# color_sensor.net
KiCad netlist of a schematic drawn in EAGLE
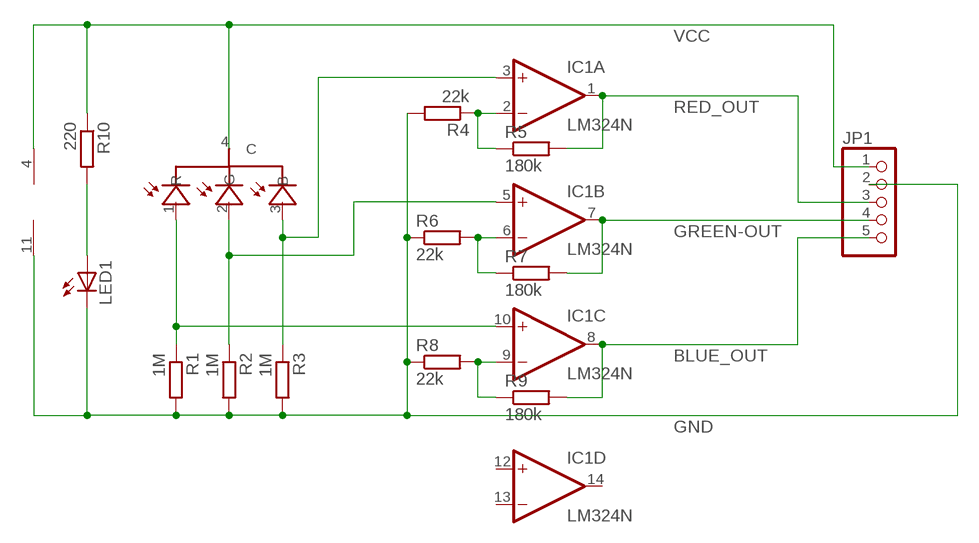
[diagram p0: schematic, sheet 1]

(export (version "E")
  (design (tool "Eeschema 10.0.6"))
  (components
    (comp (ref "IC1")
      (value "LM324N")
      (footprint "eagle-import:DIL14")
      (libsource (lib "eagle-import") (part "LM324N"))
    )
    (comp (ref "JP1")
      (value "PINHD-1X5")
      (footprint "eagle-import:1X05")
      (libsource (lib "eagle-import") (part "PINHD-1X5"))
    )
    (comp (ref "LED1")
      (value "LED5MM")
      (footprint "eagle-import:LED5MM")
      (libsource (lib "eagle-import") (part "LED5MM"))
    )
    (comp (ref "R1")
      (value "1M")
      (footprint "eagle-import:0207_10")
      (libsource (lib "eagle-import") (part "R-EU_0207/10"))
    )
    (comp (ref "R2")
      (value "1M")
      (footprint "eagle-import:0207_10")
      (libsource (lib "eagle-import") (part "R-EU_0207/10"))
    )
    (comp (ref "R3")
      (value "1M")
      (footprint "eagle-import:0207_10")
      (libsource (lib "eagle-import") (part "R-EU_0207/10"))
    )
    (comp (ref "R4")
      (value "22k")
      (footprint "eagle-import:0207_10")
      (libsource (lib "eagle-import") (part "R-EU_0207/10"))
    )
    (comp (ref "R5")
      (value "180k")
      (footprint "eagle-import:0207_10")
      (libsource (lib "eagle-import") (part "R-EU_0207/10"))
    )
    (comp (ref "R6")
      (value "22k")
      (footprint "eagle-import:0207_10")
      (libsource (lib "eagle-import") (part "R-EU_0207/10"))
    )
    (comp (ref "R7")
      (value "180k")
      (footprint "eagle-import:0207_10")
      (libsource (lib "eagle-import") (part "R-EU_0207/10"))
    )
    (comp (ref "R8")
      (value "22k")
      (footprint "eagle-import:0207_10")
      (libsource (lib "eagle-import") (part "R-EU_0207/10"))
    )
    (comp (ref "R9")
      (value "180k")
      (footprint "eagle-import:0207_10")
      (libsource (lib "eagle-import") (part "R-EU_0207/10"))
    )
    (comp (ref "R10")
      (value "220")
      (footprint "eagle-import:0207_10")
      (libsource (lib "eagle-import") (part "R-EU_0207/10"))
    )
    (comp (ref "U$1")
      (value "KPS-5130PD7C")
      (footprint "eagle-import:KPS-5130PD7C")
      (libsource (lib "eagle-import") (part "KPS-5130PD7C"))
    )
  )
  (nets
    (net (code "1") (name "/BLUE_OUT") (class "Default")
      (node (ref "IC1") (pin "8") (pinfunction "OUT_8") (pintype "output"))
      (node (ref "JP1") (pin "5") (pinfunction "5_5") (pintype "passive"))
      (node (ref "R9") (pin "2") (pinfunction "2_2") (pintype "passive"))
    )
    (net (code "2") (name "/GND") (class "Default")
      (node (ref "IC1") (pin "11") (pinfunction "V-_11") (pintype "power_in"))
      (node (ref "JP1") (pin "2") (pinfunction "2_2") (pintype "passive"))
      (node (ref "LED1") (pin "K") (pinfunction "C_K") (pintype "passive"))
      (node (ref "R1") (pin "2") (pinfunction "2_2") (pintype "passive"))
      (node (ref "R2") (pin "2") (pinfunction "2_2") (pintype "passive"))
      (node (ref "R3") (pin "2") (pinfunction "2_2") (pintype "passive"))
      (node (ref "R4") (pin "2") (pinfunction "2_2") (pintype "passive"))
      (node (ref "R6") (pin "1") (pinfunction "1_1") (pintype "passive"))
      (node (ref "R8") (pin "1") (pinfunction "1_1") (pintype "passive"))
    )
    (net (code "3") (name "/GREEN-OUT") (class "Default")
      (node (ref "IC1") (pin "7") (pinfunction "OUT_7") (pintype "output"))
      (node (ref "JP1") (pin "4") (pinfunction "4_4") (pintype "passive"))
      (node (ref "R7") (pin "2") (pinfunction "2_2") (pintype "passive"))
    )
    (net (code "4") (name "/RED_OUT") (class "Default")
      (node (ref "IC1") (pin "1") (pinfunction "OUT_1") (pintype "output"))
      (node (ref "JP1") (pin "3") (pinfunction "3_3") (pintype "passive"))
      (node (ref "R5") (pin "2") (pinfunction "2_2") (pintype "passive"))
    )
    (net (code "5") (name "/VCC") (class "Default")
      (node (ref "IC1") (pin "4") (pinfunction "V+_4") (pintype "power_in"))
      (node (ref "JP1") (pin "1") (pinfunction "1_1") (pintype "passive"))
      (node (ref "R10") (pin "1") (pinfunction "1_1") (pintype "passive"))
      (node (ref "U$1") (pin "4") (pinfunction "C_4") (pintype "bidirectional"))
    )
    (net (code "6") (name "Net-(IC1A-+IN)") (class "Default")
      (node (ref "IC1") (pin "3") (pinfunction "+IN_3") (pintype "input"))
      (node (ref "R3") (pin "1") (pinfunction "1_1") (pintype "passive"))
      (node (ref "U$1") (pin "3") (pinfunction "B_3") (pintype "bidirectional"))
    )
    (net (code "7") (name "Net-(IC1A--IN)") (class "Default")
      (node (ref "IC1") (pin "2") (pinfunction "-IN_2") (pintype "input"))
      (node (ref "R4") (pin "1") (pinfunction "1_1") (pintype "passive"))
      (node (ref "R5") (pin "1") (pinfunction "1_1") (pintype "passive"))
    )
    (net (code "8") (name "Net-(IC1B-+IN)") (class "Default")
      (node (ref "IC1") (pin "5") (pinfunction "+IN_5") (pintype "input"))
      (node (ref "R2") (pin "1") (pinfunction "1_1") (pintype "passive"))
      (node (ref "U$1") (pin "2") (pinfunction "G_2") (pintype "bidirectional"))
    )
    (net (code "9") (name "Net-(IC1B--IN)") (class "Default")
      (node (ref "IC1") (pin "6") (pinfunction "-IN_6") (pintype "input"))
      (node (ref "R6") (pin "2") (pinfunction "2_2") (pintype "passive"))
      (node (ref "R7") (pin "1") (pinfunction "1_1") (pintype "passive"))
    )
    (net (code "10") (name "Net-(IC1C-+IN)") (class "Default")
      (node (ref "IC1") (pin "10") (pinfunction "+IN_10") (pintype "input"))
      (node (ref "R1") (pin "1") (pinfunction "1_1") (pintype "passive"))
      (node (ref "U$1") (pin "1") (pinfunction "R_1") (pintype "bidirectional"))
    )
    (net (code "11") (name "Net-(IC1C--IN)") (class "Default")
      (node (ref "IC1") (pin "9") (pinfunction "-IN_9") (pintype "input"))
      (node (ref "R8") (pin "2") (pinfunction "2_2") (pintype "passive"))
      (node (ref "R9") (pin "1") (pinfunction "1_1") (pintype "passive"))
    )
    (net (code "12") (name "Net-(LED1-PadA)") (class "Default")
      (node (ref "LED1") (pin "A") (pinfunction "A_A") (pintype "passive"))
      (node (ref "R10") (pin "2") (pinfunction "2_2") (pintype "passive"))
    )
    (net (code "13") (name "unconnected-(IC1D-+IN-Pad12)") (class "Default")
      (node (ref "IC1") (pin "12") (pinfunction "+IN_12") (pintype "input"))
    )
    (net (code "14") (name "unconnected-(IC1D--IN-Pad13)") (class "Default")
      (node (ref "IC1") (pin "13") (pinfunction "-IN_13") (pintype "input"))
    )
    (net (code "15") (name "unconnected-(IC1D-OUT-Pad14)") (class "Default")
      (node (ref "IC1") (pin "14") (pinfunction "OUT_14") (pintype "output"))
    )
  )
)
